# SparkFun_Digi_XBee_Development_Board.net
KiCad netlist of a schematic drawn in EAGLE
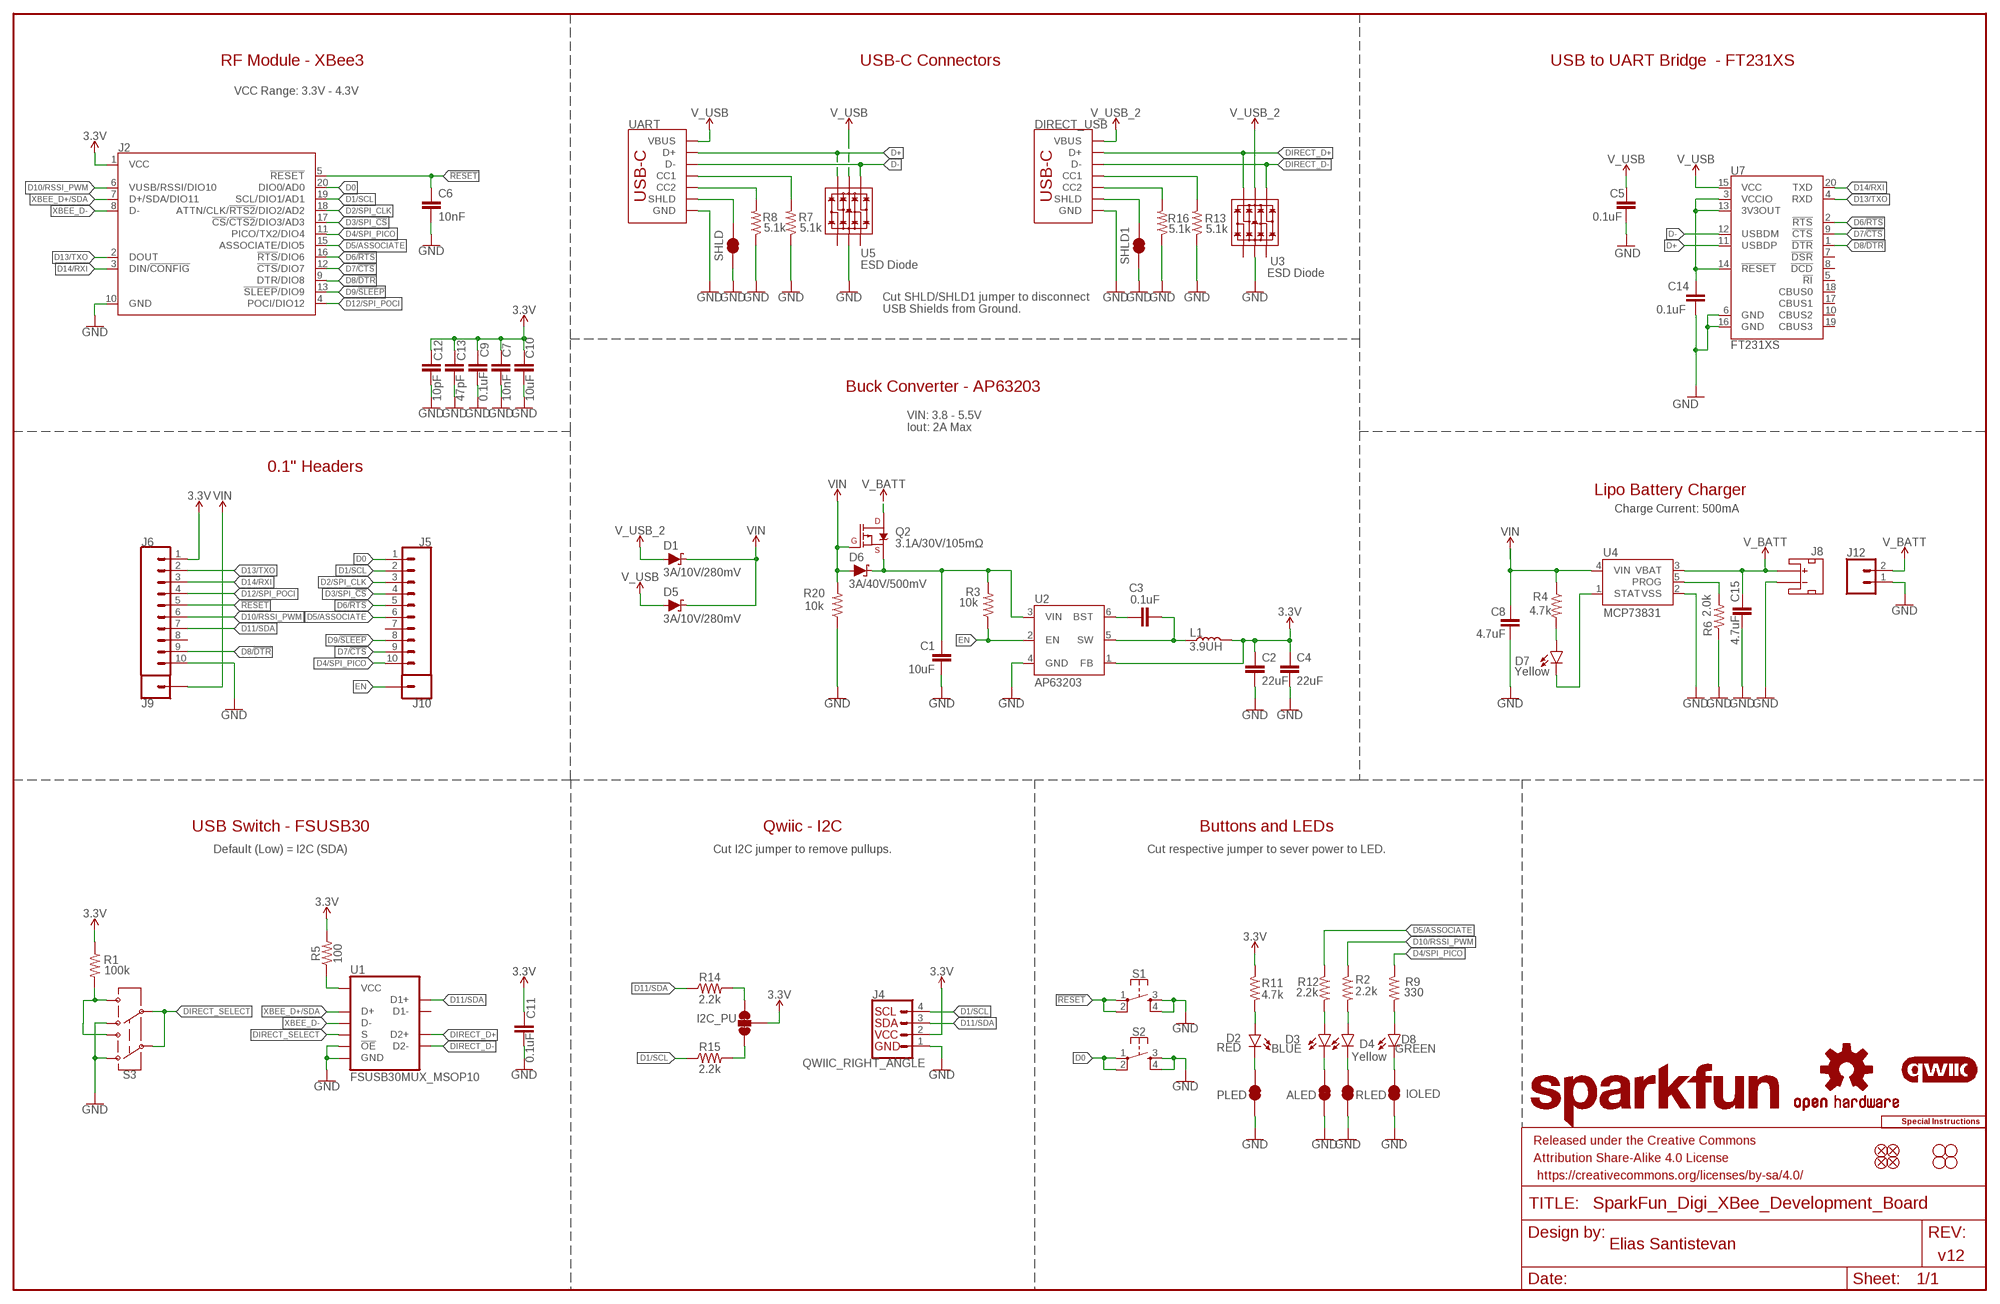
[diagram p0: schematic, sheet 1]

(export (version "E")
  (design (tool "Eeschema 10.0.6"))
  (components
    (comp (ref "ALED")
      (value "JUMPER-SMT_2_NC_TRACE_SILK")
      (footprint "eagle-import:SMT-JUMPER_2_NC_TRACE_SILK")
      (libsource (lib "eagle-import") (part "JUMPER-SMT_2_NC_TRACE_SILK"))
    )
    (comp (ref "C1")
      (value "10uF")
      (footprint "eagle-import:1210")
      (libsource (lib "eagle-import") (part "10UF-1210-50V-20%"))
    )
    (comp (ref "C2")
      (value "22uF")
      (footprint "eagle-import:0603")
      (libsource (lib "eagle-import") (part "22UF-0603-6.3V-20%"))
    )
    (comp (ref "C3")
      (value "0.1uF")
      (footprint "eagle-import:0603")
      (libsource (lib "eagle-import") (part "0.1UF-0603-25V-5%"))
    )
    (comp (ref "C4")
      (value "22uF")
      (footprint "eagle-import:0603")
      (libsource (lib "eagle-import") (part "22UF-0603-6.3V-20%"))
    )
    (comp (ref "C5")
      (value "0.1uF")
      (footprint "eagle-import:0603")
      (libsource (lib "eagle-import") (part "0.1UF-0603-25V-(+80/-20%)"))
    )
    (comp (ref "C6")
      (value "10nF")
      (footprint "eagle-import:0603")
      (libsource (lib "eagle-import") (part "10NF-0603-50V-10%"))
    )
    (comp (ref "C7")
      (value "10nF")
      (footprint "eagle-import:0603")
      (libsource (lib "eagle-import") (part "10NF-0603-50V-10%"))
    )
    (comp (ref "C8")
      (value "4.7uF")
      (footprint "eagle-import:0603")
      (libsource (lib "eagle-import") (part "4.7UF-0603-6.3V-(10%)"))
    )
    (comp (ref "C9")
      (value "0.1uF")
      (footprint "eagle-import:0603")
      (libsource (lib "eagle-import") (part "0.1UF-0603-25V-(+80/-20%)"))
    )
    (comp (ref "C10")
      (value "10uF")
      (footprint "eagle-import:0603")
      (libsource (lib "eagle-import") (part "10UF-0603-6.3V-20%"))
    )
    (comp (ref "C11")
      (value "0.1uF")
      (footprint "eagle-import:0603")
      (libsource (lib "eagle-import") (part "0.1UF-0603-25V-(+80/-20%)"))
    )
    (comp (ref "C12")
      (value "10pF")
      (footprint "eagle-import:0603")
      (libsource (lib "eagle-import") (part "10PF-0603-50V-5%"))
    )
    (comp (ref "C13")
      (value "47pF")
      (footprint "eagle-import:0603")
      (libsource (lib "eagle-import") (part "47PF-0603-50V-5%"))
    )
    (comp (ref "C14")
      (value "0.1uF")
      (footprint "eagle-import:0603")
      (libsource (lib "eagle-import") (part "0.1UF-0603-25V-(+80/-20%)"))
    )
    (comp (ref "C15")
      (value "4.7uF")
      (footprint "eagle-import:0603")
      (libsource (lib "eagle-import") (part "4.7UF-0603-35V-(20%)"))
    )
    (comp (ref "D1")
      (value "3A/10V/280mV")
      (footprint "eagle-import:SOD-323")
      (libsource (lib "eagle-import") (part "DIODE-SCHOTTKY-BAT60A"))
    )
    (comp (ref "D2")
      (value "RED")
      (footprint "eagle-import:LED-0603")
      (libsource (lib "eagle-import") (part "LED-RED_0603-KB"))
    )
    (comp (ref "D3")
      (value "BLUE")
      (footprint "eagle-import:LED-0603")
      (libsource (lib "eagle-import") (part "LED-BLUE0603"))
    )
    (comp (ref "D4")
      (value "Yellow")
      (footprint "eagle-import:LED-0603")
      (libsource (lib "eagle-import") (part "LED-YELLOW0603"))
    )
    (comp (ref "D5")
      (value "3A/10V/280mV")
      (footprint "eagle-import:SOD-323")
      (libsource (lib "eagle-import") (part "DIODE-SCHOTTKY-BAT60A"))
    )
    (comp (ref "D6")
      (value "3A/40V/500mV")
      (footprint "eagle-import:SMA-DIODE")
      (libsource (lib "eagle-import") (part "DIODE-SCHOTTKY-B340A"))
    )
    (comp (ref "D7")
      (value "Yellow")
      (footprint "eagle-import:LED-0603")
      (libsource (lib "eagle-import") (part "LED-YELLOW0603"))
    )
    (comp (ref "D8")
      (value "GREEN")
      (footprint "eagle-import:LED-0603")
      (libsource (lib "eagle-import") (part "LED-GREEN0603"))
    )
    (comp (ref "DIRECT_USB")
      (value "USB Female Type C Connector")
      (footprint "eagle-import:USB-C-16P-4LAYER-ISOLATED")
      (libsource (lib "eagle-import") (part "USB_C_4-LAYER-ISOLATED"))
    )
    (comp (ref "FD1")
      (value "FIDUCIAL1X2")
      (footprint "eagle-import:FIDUCIAL-1X2")
      (libsource (lib "eagle-import") (part "FIDUCIAL1X2"))
    )
    (comp (ref "FD2")
      (value "FIDUCIAL1X2")
      (footprint "eagle-import:FIDUCIAL-1X2")
      (libsource (lib "eagle-import") (part "FIDUCIAL1X2"))
    )
    (comp (ref "FD3")
      (value "FIDUCIAL1X2")
      (footprint "eagle-import:FIDUCIAL-1X2")
      (libsource (lib "eagle-import") (part "FIDUCIAL1X2"))
    )
    (comp (ref "FD4")
      (value "FIDUCIAL1X2")
      (footprint "eagle-import:FIDUCIAL-1X2")
      (libsource (lib "eagle-import") (part "FIDUCIAL1X2"))
    )
    (comp (ref "FRAME1")
      (value "FRAME-LEDGER")
      (footprint "eagle-import:CREATIVE_COMMONS")
      (libsource (lib "eagle-import") (part "FRAME-LEDGER"))
    )
    (comp (ref "H1")
      (value "STAND-OFFTIGHT")
      (footprint "eagle-import:STAND-OFF-TIGHT")
      (libsource (lib "eagle-import") (part "STAND-OFFTIGHT"))
    )
    (comp (ref "H2")
      (value "STAND-OFFTIGHT")
      (footprint "eagle-import:STAND-OFF-TIGHT")
      (libsource (lib "eagle-import") (part "STAND-OFFTIGHT"))
    )
    (comp (ref "H3")
      (value "STAND-OFFTIGHT")
      (footprint "eagle-import:STAND-OFF-TIGHT")
      (libsource (lib "eagle-import") (part "STAND-OFFTIGHT"))
    )
    (comp (ref "H4")
      (value "STAND-OFFTIGHT")
      (footprint "eagle-import:STAND-OFF-TIGHT")
      (libsource (lib "eagle-import") (part "STAND-OFFTIGHT"))
    )
    (comp (ref "I2C_PU")
      (value "JUMPER-SMT_3_2-NC_TRACE_SILK")
      (footprint "eagle-import:SMT-JUMPER_3_2-NC_TRACE_SILK")
      (libsource (lib "eagle-import") (part "JUMPER-SMT_3_2-NC_TRACE_SILK"))
    )
    (comp (ref "IOLED")
      (value "JUMPER-SMT_2_NC_TRACE_SILK")
      (footprint "eagle-import:SMT-JUMPER_2_NC_TRACE_SILK")
      (libsource (lib "eagle-import") (part "JUMPER-SMT_2_NC_TRACE_SILK"))
    )
    (comp (ref "J2")
      (value "XBEE_UPDATEXBEE_SMD")
      (footprint "eagle-import:XBEE3-SMD")
      (libsource (lib "eagle-import") (part "XBEE_UPDATEXBEE_SMD"))
    )
    (comp (ref "J4")
      (value "QWIIC_RIGHT_ANGLE")
      (footprint "eagle-import:JST04_1MM_RA")
      (libsource (lib "eagle-import") (part "QWIIC_CONNECTORJS-1MM"))
    )
    (comp (ref "J5")
      (value "CONN_10NO_SILK_PTH_FEMALE")
      (footprint "eagle-import:1X10_NO_SILK")
      (libsource (lib "eagle-import") (part "CONN_10NO_SILK_PTH_FEMALE"))
    )
    (comp (ref "J6")
      (value "CONN_10NO_SILK_PTH_FEMALE")
      (footprint "eagle-import:1X10_NO_SILK")
      (libsource (lib "eagle-import") (part "CONN_10NO_SILK_PTH_FEMALE"))
    )
    (comp (ref "J8")
      (value "JST_2MM_MALE")
      (footprint "eagle-import:JST-2-SMD")
      (libsource (lib "eagle-import") (part "JST_2MM_MALE"))
    )
    (comp (ref "J9")
      (value "CONN_01PTH_NO_SILK_STAND")
      (footprint "eagle-import:1X01_NO_SILK_STAND")
      (libsource (lib "eagle-import") (part "CONN_01PTH_NO_SILK_STAND"))
    )
    (comp (ref "J10")
      (value "CONN_01PTH_NO_SILK_STAND")
      (footprint "eagle-import:1X01_NO_SILK_STAND")
      (libsource (lib "eagle-import") (part "CONN_01PTH_NO_SILK_STAND"))
    )
    (comp (ref "J12")
      (value "CONN_021X02_NO_SILK")
      (footprint "eagle-import:1X02_NO_SILK")
      (libsource (lib "eagle-import") (part "CONN_021X02_NO_SILK"))
    )
    (comp (ref "L1")
      (value "3.9UH")
      (footprint "eagle-import:INDUCTOR_3.9UH")
      (libsource (lib "eagle-import") (part "3.9UH"))
    )
    (comp (ref "LOGO1")
      (value "SFE_LOGO_NAME.2_INCH")
      (footprint "eagle-import:SFE_LOGO_NAME_.2")
      (libsource (lib "eagle-import") (part "SFE_LOGO_NAME.2_INCH"))
    )
    (comp (ref "LOGO2")
      (value "OSHW-LOGOS")
      (footprint "eagle-import:OSHW-LOGO-S")
      (libsource (lib "eagle-import") (part "OSHW-LOGOS"))
    )
    (comp (ref "LOGO3")
      (value "QWIIC_LOGO_5MM")
      (footprint "eagle-import:QWIIC_5MM")
      (libsource (lib "eagle-import") (part "QWIIC_LOGO_5MM"))
    )
    (comp (ref "LOGO5")
      (value "SPECIAL_INSTRUCTIONS-ORDERING")
      (footprint "eagle-import:ORDERING_INSTRUCTIONS")
      (libsource (lib "eagle-import") (part "SPECIAL_INSTRUCTIONS-ORDERING"))
    )
    (comp (ref "PLED")
      (value "JUMPER-SMT_2_NC_TRACE_SILK")
      (footprint "eagle-import:SMT-JUMPER_2_NC_TRACE_SILK")
      (libsource (lib "eagle-import") (part "JUMPER-SMT_2_NC_TRACE_SILK"))
    )
    (comp (ref "Q2")
      (value "3.1A/30V/105mΩ")
      (footprint "eagle-import:SOT23-3")
      (libsource (lib "eagle-import") (part "MOSFET_PCH-DMG2307L"))
    )
    (comp (ref "R1")
      (value "100k")
      (footprint "eagle-import:0603")
      (libsource (lib "eagle-import") (part "100KOHM-0603-1/10W-1%"))
    )
    (comp (ref "R2")
      (value "2.2k")
      (footprint "eagle-import:0603")
      (libsource (lib "eagle-import") (part "2.2KOHM-0603-1/10W-1%"))
    )
    (comp (ref "R3")
      (value "10k")
      (footprint "eagle-import:0603")
      (libsource (lib "eagle-import") (part "10KOHM-0603-1/10W-1%"))
    )
    (comp (ref "R4")
      (value "4.7k")
      (footprint "eagle-import:0603")
      (libsource (lib "eagle-import") (part "4.7KOHM-0603-1/10W-1%"))
    )
    (comp (ref "R5")
      (value "100")
      (footprint "eagle-import:0603")
      (libsource (lib "eagle-import") (part "100OHM-0603-1/10W-1%"))
    )
    (comp (ref "R6")
      (value "2.0k")
      (footprint "eagle-import:0603")
      (libsource (lib "eagle-import") (part "2.0KOHM-0603-1/10W-5%"))
    )
    (comp (ref "R7")
      (value "5.1k")
      (footprint "eagle-import:0603")
      (libsource (lib "eagle-import") (part "5.1KOHM5.1KOHM-0603-1/10W-1%"))
    )
    (comp (ref "R8")
      (value "5.1k")
      (footprint "eagle-import:0603")
      (libsource (lib "eagle-import") (part "5.1KOHM5.1KOHM-0603-1/10W-1%"))
    )
    (comp (ref "R9")
      (value "330")
      (footprint "eagle-import:0603")
      (libsource (lib "eagle-import") (part "330OHM-0603-1/10W-1%"))
    )
    (comp (ref "R11")
      (value "4.7k")
      (footprint "eagle-import:0603")
      (libsource (lib "eagle-import") (part "4.7KOHM-0603-1/10W-1%"))
    )
    (comp (ref "R12")
      (value "2.2k")
      (footprint "eagle-import:0603")
      (libsource (lib "eagle-import") (part "2.2KOHM-0603-1/10W-1%"))
    )
    (comp (ref "R13")
      (value "5.1k")
      (footprint "eagle-import:0603")
      (libsource (lib "eagle-import") (part "5.1KOHM5.1KOHM-0603-1/10W-1%"))
    )
    (comp (ref "R14")
      (value "2.2k")
      (footprint "eagle-import:0603")
      (libsource (lib "eagle-import") (part "2.2KOHM-0603-1/10W-1%"))
    )
    (comp (ref "R15")
      (value "2.2k")
      (footprint "eagle-import:0603")
      (libsource (lib "eagle-import") (part "2.2KOHM-0603-1/10W-1%"))
    )
    (comp (ref "R16")
      (value "5.1k")
      (footprint "eagle-import:0603")
      (libsource (lib "eagle-import") (part "5.1KOHM5.1KOHM-0603-1/10W-1%"))
    )
    (comp (ref "R20")
      (value "10k")
      (footprint "eagle-import:0603")
      (libsource (lib "eagle-import") (part "10KOHM-0603-1/10W-1%"))
    )
    (comp (ref "RLED")
      (value "JUMPER-SMT_2_NC_TRACE_SILK")
      (footprint "eagle-import:SMT-JUMPER_2_NC_TRACE_SILK")
      (libsource (lib "eagle-import") (part "JUMPER-SMT_2_NC_TRACE_SILK"))
    )
    (comp (ref "S1")
      (value "MOMENTARY-SWITCH-SPST-2-SMD-5.2MM-TALL")
      (footprint "eagle-import:TACTILE_SWITCH_SMD_5.2MM")
      (libsource (lib "eagle-import") (part "MOMENTARY-SWITCH-SPST-2-SMD-5.2MM-TALL"))
    )
    (comp (ref "S2")
      (value "MOMENTARY-SWITCH-SPST-2-SMD-5.2MM-TALL")
      (footprint "eagle-import:TACTILE_SWITCH_SMD_5.2MM")
      (libsource (lib "eagle-import") (part "MOMENTARY-SWITCH-SPST-2-SMD-5.2MM-TALL"))
    )
    (comp (ref "S3")
      (value "SWITCH-DPDT-SMD-AYZ0202")
      (footprint "eagle-import:SWITCH_DPDT_SMD_AYZ0202")
      (libsource (lib "eagle-import") (part "SWITCH-DPDT-SMD-AYZ0202"))
    )
    (comp (ref "SHLD")
      (value "JUMPER-SMT_2_NC_TRACE_SILK")
      (footprint "eagle-import:SMT-JUMPER_2_NC_TRACE_SILK")
      (libsource (lib "eagle-import") (part "JUMPER-SMT_2_NC_TRACE_SILK"))
    )
    (comp (ref "SHLD1")
      (value "JUMPER-SMT_2_NC_TRACE_SILK")
      (footprint "eagle-import:SMT-JUMPER_2_NC_TRACE_SILK")
      (libsource (lib "eagle-import") (part "JUMPER-SMT_2_NC_TRACE_SILK"))
    )
    (comp (ref "U1")
      (value "FSUSB30MUX_MSOP10")
      (footprint "eagle-import:MSOP10")
      (libsource (lib "eagle-import") (part "FSUSB30MUX_MSOP10"))
    )
    (comp (ref "U2")
      (value "AP63203")
      (footprint "eagle-import:SOT23-6")
      (libsource (lib "eagle-import") (part "AP63203"))
    )
    (comp (ref "U3")
      (value "ESD Diode")
      (footprint "eagle-import:SOT-23-6")
      (libsource (lib "eagle-import") (part "TVS_DIODE_ARRAY_DT1042-04SO-7"))
    )
    (comp (ref "U4")
      (value "MCP73831")
      (footprint "eagle-import:SOT23-5")
      (libsource (lib "eagle-import") (part "MCP73831"))
    )
    (comp (ref "U5")
      (value "ESD Diode")
      (footprint "eagle-import:SOT-23-6")
      (libsource (lib "eagle-import") (part "TVS_DIODE_ARRAY_DT1042-04SO-7"))
    )
    (comp (ref "U7")
      (value "FT231XS")
      (footprint "eagle-import:SSOP20_L")
      (libsource (lib "eagle-import") (part "FT231XS"))
    )
    (comp (ref "UART")
      (value "USB Female Type C Connector")
      (footprint "eagle-import:USB-C-16P-4LAYER-ISOLATED")
      (libsource (lib "eagle-import") (part "USB_C_4-LAYER-ISOLATED"))
    )
  )
  (nets
    (net (code "1") (name "/D3{slash}SPI_~{CS}") (class "Default")
      (node (ref "J2") (pin "17") (pinfunction "~{CS}/~{CTS2}/DIO3/AD3_17") (pintype "bidirectional"))
      (node (ref "J5") (pin "4") (pinfunction "4_4") (pintype "passive"))
    )
    (net (code "2") (name "/D6{slash}~{RTS}") (class "Default")
      (node (ref "J2") (pin "16") (pinfunction "~{RTS}/DIO6_16") (pintype "input"))
      (node (ref "J5") (pin "5") (pinfunction "5_5") (pintype "passive"))
      (node (ref "U7") (pin "2") (pinfunction "~{RTS}_2") (pintype "bidirectional"))
    )
    (net (code "3") (name "/D7{slash}~{CTS}") (class "Default")
      (node (ref "J2") (pin "12") (pinfunction "~{CTS}/DIO7_12") (pintype "output"))
      (node (ref "J5") (pin "9") (pinfunction "9_9") (pintype "passive"))
      (node (ref "U7") (pin "9") (pinfunction "~{CTS}_9") (pintype "bidirectional"))
    )
    (net (code "4") (name "/D8{slash}~{DTR}") (class "Default")
      (node (ref "J2") (pin "9") (pinfunction "DTR/DIO8_9") (pintype "bidirectional"))
      (node (ref "J6") (pin "9") (pinfunction "9_9") (pintype "passive"))
      (node (ref "U7") (pin "1") (pinfunction "~{DTR}_1") (pintype "bidirectional"))
    )
    (net (code "5") (name "/D9{slash}~{SLEEP}") (class "Default")
      (node (ref "J2") (pin "13") (pinfunction "~{SLEEP}/DIO9_13") (pintype "bidirectional"))
      (node (ref "J5") (pin "8") (pinfunction "8_8") (pintype "passive"))
    )
    (net (code "6") (name "/~{RESET}") (class "Default")
      (node (ref "C6") (pin "1") (pinfunction "1_1") (pintype "passive"))
      (node (ref "J2") (pin "5") (pinfunction "~{RESET}_5") (pintype "input"))
      (node (ref "J6") (pin "5") (pinfunction "5_5") (pintype "passive"))
      (node (ref "S1") (pin "1") (pinfunction "1_1") (pintype "passive"))
      (node (ref "S1") (pin "2") (pinfunction "2_2") (pintype "passive"))
    )
    (net (code "7") (name "3.3V") (class "Default")
      (node (ref "C10") (pin "1") (pinfunction "1_1") (pintype "passive"))
      (node (ref "C11") (pin "1") (pinfunction "1_1") (pintype "passive"))
      (node (ref "C12") (pin "1") (pinfunction "1_1") (pintype "passive"))
      (node (ref "C13") (pin "1") (pinfunction "1_1") (pintype "passive"))
      (node (ref "C2") (pin "1") (pinfunction "1_1") (pintype "passive"))
      (node (ref "C4") (pin "1") (pinfunction "1_1") (pintype "passive"))
      (node (ref "C7") (pin "1") (pinfunction "1_1") (pintype "passive"))
      (node (ref "C9") (pin "1") (pinfunction "1_1") (pintype "passive"))
      (node (ref "I2C_PU") (pin "2") (pinfunction "2_2") (pintype "passive"))
      (node (ref "J2") (pin "1") (pinfunction "VCC_1") (pintype "power_in"))
      (node (ref "J4") (pin "2") (pinfunction "2_2") (pintype "power_in"))
      (node (ref "J6") (pin "1") (pinfunction "1_1") (pintype "passive"))
      (node (ref "L1") (pin "P$2") (pinfunction "2_P$2") (pintype "passive"))
      (node (ref "R1") (pin "1") (pinfunction "1_1") (pintype "passive"))
      (node (ref "R11") (pin "1") (pinfunction "1_1") (pintype "passive"))
      (node (ref "R5") (pin "2") (pinfunction "2_2") (pintype "passive"))
      (node (ref "U2") (pin "1") (pinfunction "FB_1") (pintype "bidirectional"))
    )
    (net (code "8") (name "D+") (class "Default")
      (node (ref "U5") (pin "6") (pinfunction "IO4_6") (pintype "bidirectional"))
      (node (ref "U7") (pin "11") (pinfunction "USBDP_11") (pintype "bidirectional"))
      (node (ref "UART") (pin "A6") (pinfunction "D+_A6") (pintype "bidirectional"))
      (node (ref "UART") (pin "B6") (pinfunction "D+_B6") (pintype "bidirectional"))
    )
    (net (code "9") (name "D-") (class "Default")
      (node (ref "U5") (pin "4") (pinfunction "IO3_4") (pintype "bidirectional"))
      (node (ref "U7") (pin "12") (pinfunction "USBDM_12") (pintype "bidirectional"))
      (node (ref "UART") (pin "A7") (pinfunction "D-_A7") (pintype "bidirectional"))
      (node (ref "UART") (pin "B7") (pinfunction "D-_B7") (pintype "bidirectional"))
    )
    (net (code "10") (name "D0") (class "Default")
      (node (ref "J2") (pin "20") (pinfunction "DIO0/AD0_20") (pintype "bidirectional"))
      (node (ref "J5") (pin "1") (pinfunction "1_1") (pintype "passive"))
      (node (ref "S2") (pin "1") (pinfunction "1_1") (pintype "passive"))
      (node (ref "S2") (pin "2") (pinfunction "2_2") (pintype "passive"))
    )
    (net (code "11") (name "D1{slash}SCL") (class "Default")
      (node (ref "J2") (pin "19") (pinfunction "SCL/DIO1/AD1_19") (pintype "bidirectional"))
      (node (ref "J4") (pin "4") (pinfunction "4_4") (pintype "passive"))
      (node (ref "J5") (pin "2") (pinfunction "2_2") (pintype "passive"))
      (node (ref "R15") (pin "1") (pinfunction "1_1") (pintype "passive"))
    )
    (net (code "12") (name "D2{slash}SPI_CLK") (class "Default")
      (node (ref "J2") (pin "18") (pinfunction "ATTN/CLK/~{RTS2}/DIO2/AD2_18") (pintype "bidirectional"))
      (node (ref "J5") (pin "3") (pinfunction "3_3") (pintype "passive"))
    )
    (net (code "13") (name "D4{slash}SPI_PICO") (class "Default")
      (node (ref "J2") (pin "11") (pinfunction "PICO/TX2/DIO4_11") (pintype "bidirectional"))
      (node (ref "J5") (pin "10") (pinfunction "10_10") (pintype "passive"))
      (node (ref "R9") (pin "1") (pinfunction "1_1") (pintype "passive"))
    )
    (net (code "14") (name "D5{slash}ASSOCIATE") (class "Default")
      (node (ref "J2") (pin "15") (pinfunction "ASSOCIATE/DIO5_15") (pintype "bidirectional"))
      (node (ref "J5") (pin "6") (pinfunction "6_6") (pintype "passive"))
      (node (ref "R12") (pin "1") (pinfunction "1_1") (pintype "passive"))
    )
    (net (code "15") (name "D10{slash}RSSI_PWM") (class "Default")
      (node (ref "J2") (pin "6") (pinfunction "VUSB/RSSI/DIO10_6") (pintype "bidirectional"))
      (node (ref "J6") (pin "6") (pinfunction "6_6") (pintype "passive"))
      (node (ref "R2") (pin "1") (pinfunction "1_1") (pintype "passive"))
    )
    (net (code "16") (name "D11{slash}SDA") (class "Default")
      (node (ref "J4") (pin "3") (pinfunction "3_3") (pintype "passive"))
      (node (ref "J6") (pin "7") (pinfunction "7_7") (pintype "passive"))
      (node (ref "R14") (pin "1") (pinfunction "1_1") (pintype "passive"))
      (node (ref "U1") (pin "2") (pinfunction "D1+_2") (pintype "bidirectional"))
    )
    (net (code "17") (name "D12{slash}SPI_POCI") (class "Default")
      (node (ref "J2") (pin "4") (pinfunction "POCI/DIO12_4") (pintype "bidirectional"))
      (node (ref "J6") (pin "4") (pinfunction "4_4") (pintype "passive"))
    )
    (net (code "18") (name "D13{slash}TXO") (class "Default")
      (node (ref "J2") (pin "2") (pinfunction "DOUT_2") (pintype "output"))
      (node (ref "J6") (pin "2") (pinfunction "2_2") (pintype "passive"))
      (node (ref "U7") (pin "4") (pinfunction "RXD_4") (pintype "bidirectional"))
    )
    (net (code "19") (name "D14{slash}RXI") (class "Default")
      (node (ref "J2") (pin "3") (pinfunction "DIN/~{CONFIG}_3") (pintype "input"))
      (node (ref "J6") (pin "3") (pinfunction "3_3") (pintype "passive"))
      (node (ref "U7") (pin "20") (pinfunction "TXD_20") (pintype "bidirectional"))
    )
    (net (code "20") (name "DIRECT_D+") (class "Default")
      (node (ref "DIRECT_USB") (pin "A6") (pinfunction "D+_A6") (pintype "bidirectional"))
      (node (ref "DIRECT_USB") (pin "B6") (pinfunction "D+_B6") (pintype "bidirectional"))
      (node (ref "U1") (pin "3") (pinfunction "D2+_3") (pintype "bidirectional"))
      (node (ref "U3") (pin "6") (pinfunction "IO4_6") (pintype "bidirectional"))
    )
    (net (code "21") (name "DIRECT_D-") (class "Default")
      (node (ref "DIRECT_USB") (pin "A7") (pinfunction "D-_A7") (pintype "bidirectional"))
      (node (ref "DIRECT_USB") (pin "B7") (pinfunction "D-_B7") (pintype "bidirectional"))
      (node (ref "U1") (pin "7") (pinfunction "D2-_7") (pintype "bidirectional"))
      (node (ref "U3") (pin "4") (pinfunction "IO3_4") (pintype "bidirectional"))
    )
    (net (code "22") (name "DIRECT_SELECT") (class "Default")
      (node (ref "S3") (pin "2") (pinfunction "2_2") (pintype "bidirectional"))
      (node (ref "S3") (pin "5") (pinfunction "5_5") (pintype "bidirectional"))
      (node (ref "U1") (pin "1") (pinfunction "S_1") (pintype "bidirectional"))
    )
    (net (code "23") (name "EN") (class "Default")
      (node (ref "J10") (pin "1") (pinfunction "1_1") (pintype "passive"))
      (node (ref "R3") (pin "1") (pinfunction "1_1") (pintype "passive"))
      (node (ref "U2") (pin "2") (pinfunction "EN_2") (pintype "bidirectional"))
    )
    (net (code "24") (name "GND") (class "Default")
      (node (ref "ALED") (pin "1") (pinfunction "1_1") (pintype "passive"))
      (node (ref "C1") (pin "2") (pinfunction "2_2") (pintype "passive"))
      (node (ref "C10") (pin "2") (pinfunction "2_2") (pintype "passive"))
      (node (ref "C11") (pin "2") (pinfunction "2_2") (pintype "passive"))
      (node (ref "C12") (pin "2") (pinfunction "2_2") (pintype "passive"))
      (node (ref "C13") (pin "2") (pinfunction "2_2") (pintype "passive"))
      (node (ref "C14") (pin "2") (pinfunction "2_2") (pintype "passive"))
      (node (ref "C15") (pin "2") (pinfunction "2_2") (pintype "passive"))
      (node (ref "C2") (pin "2") (pinfunction "2_2") (pintype "passive"))
      (node (ref "C4") (pin "2") (pinfunction "2_2") (pintype "passive"))
      (node (ref "C5") (pin "2") (pinfunction "2_2") (pintype "passive"))
      (node (ref "C6") (pin "2") (pinfunction "2_2") (pintype "passive"))
      (node (ref "C7") (pin "2") (pinfunction "2_2") (pintype "passive"))
      (node (ref "C8") (pin "2") (pinfunction "2_2") (pintype "passive"))
      (node (ref "C9") (pin "2") (pinfunction "2_2") (pintype "passive"))
      (node (ref "DIRECT_USB") (pin "GND") (pinfunction "GND_GND") (pintype "bidirectional"))
      (node (ref "DIRECT_USB") (pin "GND2") (pinfunction "GND_GND2") (pintype "bidirectional"))
      (node (ref "IOLED") (pin "1") (pinfunction "1_1") (pintype "passive"))
      (node (ref "J12") (pin "1") (pinfunction "1_1") (pintype "passive"))
      (node (ref "J2") (pin "10") (pinfunction "GND_10") (pintype "power_in"))
      (node (ref "J4") (pin "1") (pinfunction "1_1") (pintype "power_in"))
      (node (ref "J6") (pin "10") (pinfunction "10_10") (pintype "passive"))
      (node (ref "J8") (pin "1") (pinfunction "-_1") (pintype "bidirectional"))
      (node (ref "PLED") (pin "1") (pinfunction "1_1") (pintype "passive"))
      (node (ref "R13") (pin "1") (pinfunction "1_1") (pintype "passive"))
      (node (ref "R16") (pin "1") (pinfunction "1_1") (pintype "passive"))
      (node (ref "R20") (pin "1") (pinfunction "1_1") (pintype "passive"))
      (node (ref "R6") (pin "1") (pinfunction "1_1") (pintype "passive"))
      (node (ref "R7") (pin "1") (pinfunction "1_1") (pintype "passive"))
      (node (ref "R8") (pin "1") (pinfunction "1_1") (pintype "passive"))
      (node (ref "RLED") (pin "1") (pinfunction "1_1") (pintype "passive"))
      (node (ref "S1") (pin "3") (pinfunction "3_3") (pintype "passive"))
      (node (ref "S1") (pin "4") (pinfunction "4_4") (pintype "passive"))
      (node (ref "S2") (pin "3") (pinfunction "3_3") (pintype "passive"))
      (node (ref "S2") (pin "4") (pinfunction "4_4") (pintype "passive"))
      (node (ref "S3") (pin "3") (pinfunction "3_3") (pintype "bidirectional"))
      (node (ref "S3") (pin "6") (pinfunction "6_6") (pintype "bidirectional"))
      (node (ref "SHLD") (pin "1") (pinfunction "1_1") (pintype "passive"))
      (node (ref "SHLD1") (pin "1") (pinfunction "1_1") (pintype "passive"))
      (node (ref "U1") (pin "5") (pinfunction "GND_5") (pintype "bidirectional"))
      (node (ref "U1") (pin "9") (pinfunction "~{OE}_9") (pintype "bidirectional"))
      (node (ref "U2") (pin "4") (pinfunction "GND_4") (pintype "bidirectional"))
      (node (ref "U3") (pin "2") (pinfunction "VSS_2") (pintype "bidirectional"))
      (node (ref "U4") (pin "2") (pinfunction "VSS_2") (pintype "power_in"))
      (node (ref "U5") (pin "2") (pinfunction "VSS_2") (pintype "bidirectional"))
      (node (ref "U7") (pin "16") (pinfunction "GND_16") (pintype "bidirectional"))
      (node (ref "U7") (pin "6") (pinfunction "GND_6") (pintype "bidirectional"))
      (node (ref "UART") (pin "GND") (pinfunction "GND_GND") (pintype "bidirectional"))
      (node (ref "UART") (pin "GND2") (pinfunction "GND_GND2") (pintype "bidirectional"))
    )
    (net (code "25") (name "Net-(ALED-Pad2)") (class "Default")
      (node (ref "ALED") (pin "2") (pinfunction "2_2") (pintype "passive"))
      (node (ref "D3") (pin "C") (pinfunction "C_C") (pintype "passive"))
    )
    (net (code "26") (name "Net-(D2-PadA)") (class "Default")
      (node (ref "D2") (pin "A") (pinfunction "A_A") (pintype "passive"))
      (node (ref "R11") (pin "2") (pinfunction "2_2") (pintype "passive"))
    )
    (net (code "27") (name "Net-(D2-PadC)") (class "Default")
      (node (ref "D2") (pin "C") (pinfunction "C_C") (pintype "passive"))
      (node (ref "PLED") (pin "2") (pinfunction "2_2") (pintype "passive"))
    )
    (net (code "28") (name "Net-(D3-PadA)") (class "Default")
      (node (ref "D3") (pin "A") (pinfunction "A_A") (pintype "passive"))
      (node (ref "R12") (pin "2") (pinfunction "2_2") (pintype "passive"))
    )
    (net (code "29") (name "Net-(D4-PadA)") (class "Default")
      (node (ref "D4") (pin "A") (pinfunction "A_A") (pintype "passive"))
      (node (ref "R2") (pin "2") (pinfunction "2_2") (pintype "passive"))
    )
    (net (code "30") (name "Net-(D4-PadC)") (class "Default")
      (node (ref "D4") (pin "C") (pinfunction "C_C") (pintype "passive"))
      (node (ref "RLED") (pin "2") (pinfunction "2_2") (pintype "passive"))
    )
    (net (code "31") (name "Net-(D7-PadA)") (class "Default")
      (node (ref "D7") (pin "A") (pinfunction "A_A") (pintype "passive"))
      (node (ref "R4") (pin "2") (pinfunction "2_2") (pintype "passive"))
    )
    (net (code "32") (name "Net-(D8-PadA)") (class "Default")
      (node (ref "D8") (pin "A") (pinfunction "A_A") (pintype "passive"))
      (node (ref "R9") (pin "2") (pinfunction "2_2") (pintype "passive"))
    )
    (net (code "33") (name "Net-(D8-PadC)") (class "Default")
      (node (ref "D8") (pin "C") (pinfunction "C_C") (pintype "passive"))
      (node (ref "IOLED") (pin "2") (pinfunction "2_2") (pintype "passive"))
    )
    (net (code "34") (name "Net-(DIRECT_USB-CC1)") (class "Default")
      (node (ref "DIRECT_USB") (pin "A5") (pinfunction "CC1_A5") (pintype "bidirectional"))
      (node (ref "R13") (pin "2") (pinfunction "2_2") (pintype "passive"))
    )
    (net (code "35") (name "Net-(DIRECT_USB-CC2)") (class "Default")
      (node (ref "DIRECT_USB") (pin "B5") (pinfunction "CC2_B5") (pintype "bidirectional"))
      (node (ref "R16") (pin "2") (pinfunction "2_2") (pintype "passive"))
    )
    (net (code "36") (name "Net-(DIRECT_USB-SHLD-PadSHLD1)") (class "Default")
      (node (ref "DIRECT_USB") (pin "SHLD1") (pinfunction "SHLD_SHLD1") (pintype "bidirectional"))
      (node (ref "DIRECT_USB") (pin "SHLD2") (pinfunction "SHLD_SHLD2") (pintype "bidirectional"))
      (node (ref "DIRECT_USB") (pin "SHLD3") (pinfunction "SHLD_SHLD3") (pintype "bidirectional"))
      (node (ref "DIRECT_USB") (pin "SHLD4") (pinfunction "SHLD_SHLD4") (pintype "bidirectional"))
      (node (ref "DIRECT_USB") (pin "SHLD5") (pinfunction "SHLD_SHLD5") (pintype "bidirectional"))
      (node (ref "DIRECT_USB") (pin "SHLD6") (pinfunction "SHLD_SHLD6") (pintype "bidirectional"))
      (node (ref "DIRECT_USB") (pin "SHLD7") (pinfunction "SHLD_SHLD7") (pintype "bidirectional"))
      (node (ref "DIRECT_USB") (pin "SHLD8") (pinfunction "SHLD_SHLD8") (pintype "bidirectional"))
      (node (ref "SHLD1") (pin "2") (pinfunction "2_2") (pintype "passive"))
    )
    (net (code "37") (name "Net-(I2C_PU-Pad1)") (class "Default")
      (node (ref "I2C_PU") (pin "1") (pinfunction "1_1") (pintype "passive"))
      (node (ref "R15") (pin "2") (pinfunction "2_2") (pintype "passive"))
    )
    (net (code "38") (name "Net-(I2C_PU-Pad3)") (class "Default")
      (node (ref "I2C_PU") (pin "3") (pinfunction "3_3") (pintype "passive"))
      (node (ref "R14") (pin "2") (pinfunction "2_2") (pintype "passive"))
    )
    (net (code "39") (name "Net-(L1-1)") (class "Default")
      (node (ref "C3") (pin "2") (pinfunction "2_2") (pintype "passive"))
      (node (ref "L1") (pin "P$1") (pinfunction "1_P$1") (pintype "passive"))
      (node (ref "U2") (pin "5") (pinfunction "SW_5") (pintype "bidirectional"))
    )
    (net (code "40") (name "Net-(Q2-S)") (class "Default")
      (node (ref "C1") (pin "1") (pinfunction "1_1") (pintype "passive"))
      (node (ref "D6") (pin "C") (pinfunction "C_C") (pintype "passive"))
      (node (ref "Q2") (pin "2") (pinfunction "S_2") (pintype "bidirectional"))
      (node (ref "R3") (pin "2") (pinfunction "2_2") (pintype "passive"))
      (node (ref "U2") (pin "3") (pinfunction "VIN_3") (pintype "bidirectional"))
    )
    (net (code "41") (name "Net-(R1-Pad2)") (class "Default")
      (node (ref "R1") (pin "2") (pinfunction "2_2") (pintype "passive"))
      (node (ref "S3") (pin "1") (pinfunction "1_1") (pintype "bidirectional"))
      (node (ref "S3") (pin "4") (pinfunction "4_4") (pintype "bidirectional"))
    )
    (net (code "42") (name "Net-(SHLD-Pad2)") (class "Default")
      (node (ref "SHLD") (pin "2") (pinfunction "2_2") (pintype "passive"))
      (node (ref "UART") (pin "SHLD1") (pinfunction "SHLD_SHLD1") (pintype "bidirectional"))
      (node (ref "UART") (pin "SHLD2") (pinfunction "SHLD_SHLD2") (pintype "bidirectional"))
      (node (ref "UART") (pin "SHLD3") (pinfunction "SHLD_SHLD3") (pintype "bidirectional"))
      (node (ref "UART") (pin "SHLD4") (pinfunction "SHLD_SHLD4") (pintype "bidirectional"))
      (node (ref "UART") (pin "SHLD5") (pinfunction "SHLD_SHLD5") (pintype "bidirectional"))
      (node (ref "UART") (pin "SHLD6") (pinfunction "SHLD_SHLD6") (pintype "bidirectional"))
      (node (ref "UART") (pin "SHLD7") (pinfunction "SHLD_SHLD7") (pintype "bidirectional"))
      (node (ref "UART") (pin "SHLD8") (pinfunction "SHLD_SHLD8") (pintype "bidirectional"))
    )
    (net (code "43") (name "Net-(U1-VCC)") (class "Default")
      (node (ref "R5") (pin "1") (pinfunction "1_1") (pintype "passive"))
      (node (ref "U1") (pin "10") (pinfunction "VCC_10") (pintype "bidirectional"))
    )
    (net (code "44") (name "Net-(U2-BST)") (class "Default")
      (node (ref "C3") (pin "1") (pinfunction "1_1") (pintype "passive"))
      (node (ref "U2") (pin "6") (pinfunction "BST_6") (pintype "bidirectional"))
    )
    (net (code "45") (name "Net-(U4-PROG)") (class "Default")
      (node (ref "R6") (pin "2") (pinfunction "2_2") (pintype "passive"))
      (node (ref "U4") (pin "5") (pinfunction "PROG_5") (pintype "input"))
    )
    (net (code "46") (name "Net-(U4-STAT)") (class "Default")
      (node (ref "D7") (pin "C") (pinfunction "C_C") (pintype "passive"))
      (node (ref "U4") (pin "1") (pinfunction "STAT_1") (pintype "output"))
    )
    (net (code "47") (name "Net-(U7-3V3OUT)") (class "Default")
      (node (ref "C14") (pin "1") (pinfunction "1_1") (pintype "passive"))
      (node (ref "U7") (pin "13") (pinfunction "3V3OUT_13") (pintype "bidirectional"))
      (node (ref "U7") (pin "14") (pinfunction "~{RESET}_14") (pintype "bidirectional"))
      (node (ref "U7") (pin "3") (pinfunction "VCCIO_3") (pintype "bidirectional"))
    )
    (net (code "48") (name "Net-(UART-CC1)") (class "Default")
      (node (ref "R7") (pin "2") (pinfunction "2_2") (pintype "passive"))
      (node (ref "UART") (pin "A5") (pinfunction "CC1_A5") (pintype "bidirectional"))
    )
    (net (code "49") (name "Net-(UART-CC2)") (class "Default")
      (node (ref "R8") (pin "2") (pinfunction "2_2") (pintype "passive"))
      (node (ref "UART") (pin "B5") (pinfunction "CC2_B5") (pintype "bidirectional"))
    )
    (net (code "50") (name "VIN") (class "Default")
      (node (ref "C8") (pin "1") (pinfunction "1_1") (pintype "passive"))
      (node (ref "D1") (pin "C") (pinfunction "C_C") (pintype "passive"))
      (node (ref "D5") (pin "C") (pinfunction "C_C") (pintype "passive"))
      (node (ref "D6") (pin "A") (pinfunction "A_A") (pintype "passive"))
      (node (ref "J9") (pin "1") (pinfunction "1_1") (pintype "passive"))
      (node (ref "Q2") (pin "1") (pinfunction "G_1") (pintype "bidirectional"))
      (node (ref "R20") (pin "2") (pinfunction "2_2") (pintype "passive"))
      (node (ref "R4") (pin "1") (pinfunction "1_1") (pintype "passive"))
      (node (ref "U4") (pin "4") (pinfunction "VIN_4") (pintype "power_in"))
    )
    (net (code "51") (name "V_BATT") (class "Default")
      (node (ref "C15") (pin "1") (pinfunction "1_1") (pintype "passive"))
      (node (ref "J12") (pin "2") (pinfunction "2_2") (pintype "passive"))
      (node (ref "J8") (pin "2") (pinfunction "+_2") (pintype "bidirectional"))
      (node (ref "Q2") (pin "3") (pinfunction "D_3") (pintype "bidirectional"))
      (node (ref "U4") (pin "3") (pinfunction "VBAT_3") (pintype "power_in"))
    )
    (net (code "52") (name "V_USB") (class "Default")
      (node (ref "C5") (pin "1") (pinfunction "1_1") (pintype "passive"))
      (node (ref "D5") (pin "A") (pinfunction "A_A") (pintype "passive"))
      (node (ref "U5") (pin "5") (pinfunction "VCC_5") (pintype "bidirectional"))
      (node (ref "U7") (pin "15") (pinfunction "VCC_15") (pintype "bidirectional"))
      (node (ref "UART") (pin "VBUS1") (pinfunction "VBUS_VBUS1") (pintype "bidirectional"))
      (node (ref "UART") (pin "VBUS2") (pinfunction "VBUS_VBUS2") (pintype "bidirectional"))
    )
    (net (code "53") (name "V_USB_2") (class "Default")
      (node (ref "D1") (pin "A") (pinfunction "A_A") (pintype "passive"))
      (node (ref "DIRECT_USB") (pin "VBUS1") (pinfunction "VBUS_VBUS1") (pintype "bidirectional"))
      (node (ref "DIRECT_USB") (pin "VBUS2") (pinfunction "VBUS_VBUS2") (pintype "bidirectional"))
      (node (ref "U3") (pin "5") (pinfunction "VCC_5") (pintype "bidirectional"))
    )
    (net (code "54") (name "XBEE_D+{slash}SDA") (class "Default")
      (node (ref "J2") (pin "7") (pinfunction "D+/SDA/DIO11_7") (pintype "bidirectional"))
      (node (ref "U1") (pin "4") (pinfunction "D+_4") (pintype "bidirectional"))
    )
    (net (code "55") (name "XBEE_D-") (class "Default")
      (node (ref "J2") (pin "8") (pinfunction "D-_8") (pintype "bidirectional"))
      (node (ref "U1") (pin "6") (pinfunction "D-_6") (pintype "bidirectional"))
    )
    (net (code "56") (name "unconnected-(J5-Pad7)") (class "Default")
      (node (ref "J5") (pin "7") (pinfunction "7_7") (pintype "passive"))
    )
    (net (code "57") (name "unconnected-(J6-Pad8)") (class "Default")
      (node (ref "J6") (pin "8") (pinfunction "8_8") (pintype "passive"))
    )
    (net (code "58") (name "unconnected-(J8-PAD1-PadNC1)") (class "Default")
      (node (ref "J8") (pin "NC1") (pinfunction "PAD1_NC1") (pintype "bidirectional"))
    )
    (net (code "59") (name "unconnected-(J8-PAD2-PadNC2)") (class "Default")
      (node (ref "J8") (pin "NC2") (pinfunction "PAD2_NC2") (pintype "bidirectional"))
    )
    (net (code "60") (name "unconnected-(U1-D1--Pad8)") (class "Default")
      (node (ref "U1") (pin "8") (pinfunction "D1-_8") (pintype "bidirectional"))
    )
    (net (code "61") (name "unconnected-(U3-IO1-Pad1)") (class "Default")
      (node (ref "U3") (pin "1") (pinfunction "IO1_1") (pintype "bidirectional"))
    )
    (net (code "62") (name "unconnected-(U3-IO2-Pad3)") (class "Default")
      (node (ref "U3") (pin "3") (pinfunction "IO2_3") (pintype "bidirectional"))
    )
    (net (code "63") (name "unconnected-(U5-IO1-Pad1)") (class "Default")
      (node (ref "U5") (pin "1") (pinfunction "IO1_1") (pintype "bidirectional"))
    )
    (net (code "64") (name "unconnected-(U5-IO2-Pad3)") (class "Default")
      (node (ref "U5") (pin "3") (pinfunction "IO2_3") (pintype "bidirectional"))
    )
    (net (code "65") (name "unconnected-(U7-CBUS0-Pad18)") (class "Default")
      (node (ref "U7") (pin "18") (pinfunction "CBUS0_18") (pintype "bidirectional"))
    )
    (net (code "66") (name "unconnected-(U7-CBUS1-Pad17)") (class "Default")
      (node (ref "U7") (pin "17") (pinfunction "CBUS1_17") (pintype "bidirectional"))
    )
    (net (code "67") (name "unconnected-(U7-CBUS2-Pad10)") (class "Default")
      (node (ref "U7") (pin "10") (pinfunction "CBUS2_10") (pintype "bidirectional"))
    )
    (net (code "68") (name "unconnected-(U7-CBUS3-Pad19)") (class "Default")
      (node (ref "U7") (pin "19") (pinfunction "CBUS3_19") (pintype "bidirectional"))
    )
    (net (code "69") (name "unconnected-(U7-~{DCD}-Pad8)") (class "Default")
      (node (ref "U7") (pin "8") (pinfunction "~{DCD}_8") (pintype "bidirectional"))
    )
    (net (code "70") (name "unconnected-(U7-~{DSR}-Pad7)") (class "Default")
      (node (ref "U7") (pin "7") (pinfunction "~{DSR}_7") (pintype "bidirectional"))
    )
    (net (code "71") (name "unconnected-(U7-~{RI}-Pad5)") (class "Default")
      (node (ref "U7") (pin "5") (pinfunction "~{RI}_5") (pintype "bidirectional"))
    )
  )
)
